# Microcontroller.net
KiCad netlist of a schematic drawn in Altium Designer
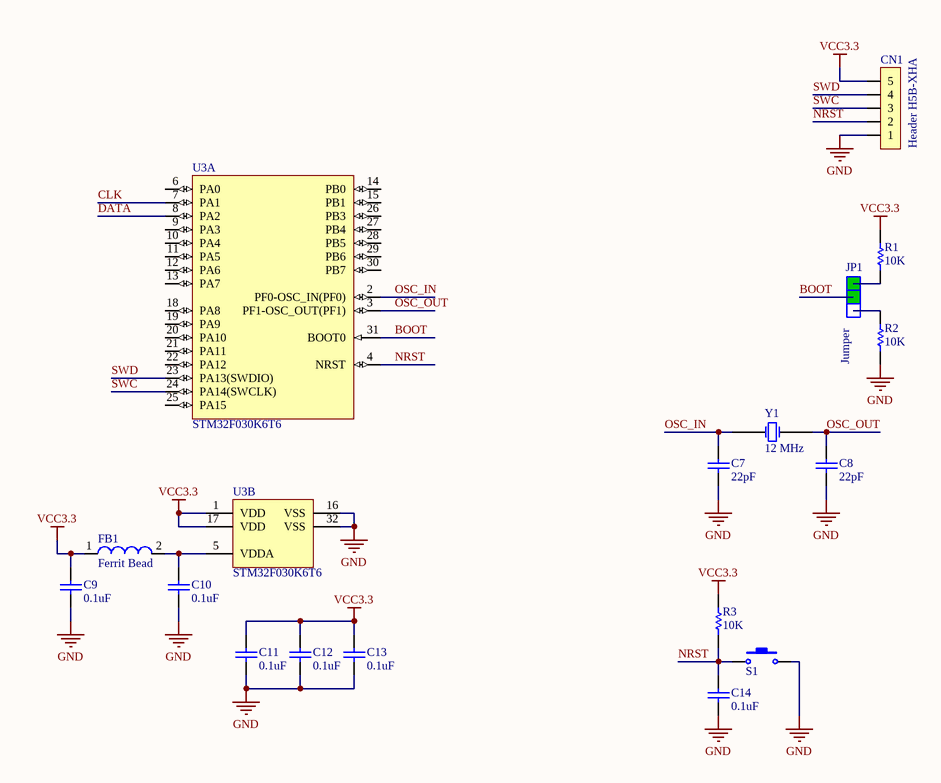
[diagram p0: Microcontroller.SchDoc]

(export (version "E")
  (design (tool "Eeschema 10.0.6"))
  (components
    (comp (ref "C7")
      (value "22pF")
      (footprint "CAPC4817X12N")
      (description "CAP 1206")
      (fields (field (name "DESIGNER") "Abbas Basereh"))
      (libsource (lib "2017AbbasBasereh9365731239 -ver1") (part "CAP SMD 1206"))
    )
    (comp (ref "C8")
      (value "22pF")
      (footprint "CAPC4817X12N")
      (description "CAP 1206")
      (fields (field (name "DESIGNER") "Abbas Basereh"))
      (libsource (lib "2017AbbasBasereh9365731239 -ver1") (part "CAP SMD 1206"))
    )
    (comp (ref "C9")
      (value "0.1uF")
      (footprint "CAPC4817X12N")
      (description "CAP 1206")
      (fields (field (name "DESIGNER") "Abbas Basereh"))
      (libsource (lib "2017AbbasBasereh9365731239 -ver1") (part "CAP SMD 1206"))
    )
    (comp (ref "C10")
      (value "0.1uF")
      (footprint "CAPC4817X12N")
      (description "CAP 1206")
      (fields (field (name "DESIGNER") "Abbas Basereh"))
      (libsource (lib "2017AbbasBasereh9365731239 -ver1") (part "CAP SMD 1206"))
    )
    (comp (ref "C11")
      (value "0.1uF")
      (footprint "CAPC4817X12N")
      (description "CAP 1206")
      (fields (field (name "DESIGNER") "Abbas Basereh"))
      (libsource (lib "2017AbbasBasereh9365731239 -ver1") (part "CAP SMD 1206"))
    )
    (comp (ref "C12")
      (value "0.1uF")
      (footprint "CAPC4817X12N")
      (description "CAP 1206")
      (fields (field (name "DESIGNER") "Abbas Basereh"))
      (libsource (lib "2017AbbasBasereh9365731239 -ver1") (part "CAP SMD 1206"))
    )
    (comp (ref "C13")
      (value "0.1uF")
      (footprint "CAPC4817X12N")
      (description "CAP 1206")
      (fields (field (name "DESIGNER") "Abbas Basereh"))
      (libsource (lib "2017AbbasBasereh9365731239 -ver1") (part "CAP SMD 1206"))
    )
    (comp (ref "C14")
      (value "0.1uF")
      (footprint "CAPC4817X12N")
      (description "CAP 1206")
      (fields (field (name "DESIGNER") "Abbas Basereh"))
      (libsource (lib "2017AbbasBasereh9365731239 -ver1") (part "CAP SMD 1206"))
    )
    (comp (ref "CN1")
      (value "Header H5B-XHA")
      (footprint "Header H5B-XHA")
      (libsource (lib "ZetaBoard_Lib") (part "Header H5B-XHA"))
    )
    (comp (ref "FB1")
      (value "Ferrit Bead")
      (footprint "1206 Ferrit Bead")
      (libsource (lib "ZetaBoard_Lib") (part "Ferrit Bead"))
    )
    (comp (ref "JP1")
      (value "Jumper")
      (footprint "Jumper Selector SMD")
      (description "Jumper Selector")
      (libsource (lib "Altium") (part "Jumper Selector"))
    )
    (comp (ref "R1")
      (value "10K")
      (footprint "RESC4817X04N")
      (description "RES 1206")
      (fields (field (name "DESIGNER") "Abbas Basereh"))
      (libsource (lib "2017AbbasBasereh9365731239 -ver1") (part "RES 1206 0.25W"))
    )
    (comp (ref "R2")
      (value "10K")
      (footprint "RESC4817X04N")
      (description "RES 1206")
      (fields (field (name "DESIGNER") "Abbas Basereh"))
      (libsource (lib "2017AbbasBasereh9365731239 -ver1") (part "RES 1206 0.25W"))
    )
    (comp (ref "R3")
      (value "10K")
      (footprint "RESC4817X04N")
      (description "RES 1206")
      (fields (field (name "DESIGNER") "Abbas Basereh"))
      (libsource (lib "2017AbbasBasereh9365731239 -ver1") (part "RES 1206 0.25W"))
    )
    (comp (ref "S1")
      (value "Switch PB")
      (footprint "Switch - Push to On")
      (description "Push Button Switch")
      (libsource (lib "Altium") (part "Switch PB"))
    )
    (comp (ref "U3")
      (value "STM32F030K6T6")
      (footprint "STM-LQFP32_N")
      (libsource (lib "STMicroelectronics STM32 F0") (part "STM32F030K6T6"))
    )
    (comp (ref "Y1")
      (value "12 MHz")
      (footprint "Crystal SMD")
      (description "XTAL Crystal")
      (fields (field (name "DESIGNER") "ABBAS BASEREH"))
      (libsource (lib "2017AbbasBasereh9365731239 -ver1") (part "XTAL_Crystal"))
    )
  )
  (nets
    (net (code "1") (name "/BOOT") (class "Default")
      (node (ref "JP1") (pin "2") (pinfunction "2_2") (pintype "passive"))
      (node (ref "U3") (pin "31") (pinfunction "BOOT0_31") (pintype "input"))
    )
    (net (code "2") (name "/CLK") (class "Default")
      (node (ref "U3") (pin "7") (pinfunction "PA1_7") (pintype "bidirectional"))
    )
    (net (code "3") (name "/DATA") (class "Default")
      (node (ref "U3") (pin "8") (pinfunction "PA2_8") (pintype "bidirectional"))
    )
    (net (code "4") (name "/NRST") (class "Default")
      (node (ref "C14") (pin "2") (pinfunction "2_2") (pintype "passive"))
      (node (ref "CN1") (pin "2") (pinfunction "2_2") (pintype "passive"))
      (node (ref "R3") (pin "1") (pinfunction "1_1") (pintype "passive"))
      (node (ref "S1") (pin "1") (pinfunction "1_1") (pintype "passive"))
      (node (ref "U3") (pin "4") (pinfunction "NRST_4") (pintype "bidirectional"))
    )
    (net (code "5") (name "/OSC_IN") (class "Default")
      (node (ref "C7") (pin "2") (pinfunction "2_2") (pintype "passive"))
      (node (ref "U3") (pin "2") (pinfunction "PF0-OSC_IN(PF0)_2") (pintype "bidirectional"))
      (node (ref "Y1") (pin "1") (pinfunction "OSC1_1") (pintype "passive"))
    )
    (net (code "6") (name "/OSC_OUT") (class "Default")
      (node (ref "C8") (pin "2") (pinfunction "2_2") (pintype "passive"))
      (node (ref "U3") (pin "3") (pinfunction "PF1-OSC_OUT(PF1)_3") (pintype "bidirectional"))
      (node (ref "Y1") (pin "2") (pinfunction "OSC2_2") (pintype "passive"))
    )
    (net (code "7") (name "/SWC") (class "Default")
      (node (ref "CN1") (pin "3") (pinfunction "3_3") (pintype "passive"))
      (node (ref "U3") (pin "24") (pinfunction "PA14(SWCLK)_24") (pintype "bidirectional"))
    )
    (net (code "8") (name "/SWD") (class "Default")
      (node (ref "CN1") (pin "4") (pinfunction "4_4") (pintype "passive"))
      (node (ref "U3") (pin "23") (pinfunction "PA13(SWDIO)_23") (pintype "bidirectional"))
    )
    (net (code "9") (name "GND") (class "Default")
      (node (ref "C10") (pin "1") (pinfunction "1_1") (pintype "passive"))
      (node (ref "C11") (pin "1") (pinfunction "1_1") (pintype "passive"))
      (node (ref "C12") (pin "1") (pinfunction "1_1") (pintype "passive"))
      (node (ref "C13") (pin "1") (pinfunction "1_1") (pintype "passive"))
      (node (ref "C14") (pin "1") (pinfunction "1_1") (pintype "passive"))
      (node (ref "C7") (pin "1") (pinfunction "1_1") (pintype "passive"))
      (node (ref "C8") (pin "1") (pinfunction "1_1") (pintype "passive"))
      (node (ref "C9") (pin "1") (pinfunction "1_1") (pintype "passive"))
      (node (ref "CN1") (pin "1") (pinfunction "1_1") (pintype "passive"))
      (node (ref "R2") (pin "1") (pinfunction "1_1") (pintype "passive"))
      (node (ref "S1") (pin "2") (pinfunction "2_2") (pintype "passive"))
      (node (ref "U3") (pin "16") (pinfunction "VSS_16") (pintype "power_in"))
      (node (ref "U3") (pin "32") (pinfunction "VSS_32") (pintype "power_in"))
    )
    (net (code "10") (name "Net-(JP1-Pad1)") (class "Default")
      (node (ref "JP1") (pin "1") (pinfunction "1_1") (pintype "passive"))
      (node (ref "R1") (pin "1") (pinfunction "1_1") (pintype "passive"))
    )
    (net (code "11") (name "Net-(JP1-Pad3)") (class "Default")
      (node (ref "JP1") (pin "3") (pinfunction "3_3") (pintype "passive"))
      (node (ref "R2") (pin "2") (pinfunction "2_2") (pintype "passive"))
    )
    (net (code "12") (name "Net-(U3B-VDDA)") (class "Default")
      (node (ref "C10") (pin "2") (pinfunction "2_2") (pintype "passive"))
      (node (ref "FB1") (pin "2") (pinfunction "2_2") (pintype "passive"))
      (node (ref "U3") (pin "5") (pinfunction "VDDA_5") (pintype "power_in"))
    )
    (net (code "13") (name "VCC3.3") (class "Default")
      (node (ref "C11") (pin "2") (pinfunction "2_2") (pintype "passive"))
      (node (ref "C12") (pin "2") (pinfunction "2_2") (pintype "passive"))
      (node (ref "C13") (pin "2") (pinfunction "2_2") (pintype "passive"))
      (node (ref "C9") (pin "2") (pinfunction "2_2") (pintype "passive"))
      (node (ref "CN1") (pin "5") (pinfunction "5_5") (pintype "passive"))
      (node (ref "FB1") (pin "1") (pinfunction "1_1") (pintype "passive"))
      (node (ref "R1") (pin "2") (pinfunction "2_2") (pintype "passive"))
      (node (ref "R3") (pin "2") (pinfunction "2_2") (pintype "passive"))
      (node (ref "U3") (pin "1") (pinfunction "VDD_1") (pintype "power_in"))
      (node (ref "U3") (pin "17") (pinfunction "VDD_17") (pintype "power_in"))
    )
    (net (code "14") (name "unconnected-(U3A-PA0-Pad6)") (class "Default")
      (node (ref "U3") (pin "6") (pinfunction "PA0_6") (pintype "bidirectional"))
    )
    (net (code "15") (name "unconnected-(U3A-PA3-Pad9)") (class "Default")
      (node (ref "U3") (pin "9") (pinfunction "PA3_9") (pintype "bidirectional"))
    )
    (net (code "16") (name "unconnected-(U3A-PA4-Pad10)") (class "Default")
      (node (ref "U3") (pin "10") (pinfunction "PA4_10") (pintype "bidirectional"))
    )
    (net (code "17") (name "unconnected-(U3A-PA5-Pad11)") (class "Default")
      (node (ref "U3") (pin "11") (pinfunction "PA5_11") (pintype "bidirectional"))
    )
    (net (code "18") (name "unconnected-(U3A-PA6-Pad12)") (class "Default")
      (node (ref "U3") (pin "12") (pinfunction "PA6_12") (pintype "bidirectional"))
    )
    (net (code "19") (name "unconnected-(U3A-PA7-Pad13)") (class "Default")
      (node (ref "U3") (pin "13") (pinfunction "PA7_13") (pintype "bidirectional"))
    )
    (net (code "20") (name "unconnected-(U3A-PA8-Pad18)") (class "Default")
      (node (ref "U3") (pin "18") (pinfunction "PA8_18") (pintype "bidirectional"))
    )
    (net (code "21") (name "unconnected-(U3A-PA9-Pad19)") (class "Default")
      (node (ref "U3") (pin "19") (pinfunction "PA9_19") (pintype "bidirectional"))
    )
    (net (code "22") (name "unconnected-(U3A-PA10-Pad20)") (class "Default")
      (node (ref "U3") (pin "20") (pinfunction "PA10_20") (pintype "bidirectional"))
    )
    (net (code "23") (name "unconnected-(U3A-PA11-Pad21)") (class "Default")
      (node (ref "U3") (pin "21") (pinfunction "PA11_21") (pintype "bidirectional"))
    )
    (net (code "24") (name "unconnected-(U3A-PA12-Pad22)") (class "Default")
      (node (ref "U3") (pin "22") (pinfunction "PA12_22") (pintype "bidirectional"))
    )
    (net (code "25") (name "unconnected-(U3A-PA15-Pad25)") (class "Default")
      (node (ref "U3") (pin "25") (pinfunction "PA15_25") (pintype "bidirectional"))
    )
    (net (code "26") (name "unconnected-(U3A-PB0-Pad14)") (class "Default")
      (node (ref "U3") (pin "14") (pinfunction "PB0_14") (pintype "bidirectional"))
    )
    (net (code "27") (name "unconnected-(U3A-PB1-Pad15)") (class "Default")
      (node (ref "U3") (pin "15") (pinfunction "PB1_15") (pintype "bidirectional"))
    )
    (net (code "28") (name "unconnected-(U3A-PB3-Pad26)") (class "Default")
      (node (ref "U3") (pin "26") (pinfunction "PB3_26") (pintype "bidirectional"))
    )
    (net (code "29") (name "unconnected-(U3A-PB4-Pad27)") (class "Default")
      (node (ref "U3") (pin "27") (pinfunction "PB4_27") (pintype "bidirectional"))
    )
    (net (code "30") (name "unconnected-(U3A-PB5-Pad28)") (class "Default")
      (node (ref "U3") (pin "28") (pinfunction "PB5_28") (pintype "bidirectional"))
    )
    (net (code "31") (name "unconnected-(U3A-PB6-Pad29)") (class "Default")
      (node (ref "U3") (pin "29") (pinfunction "PB6_29") (pintype "bidirectional"))
    )
    (net (code "32") (name "unconnected-(U3A-PB7-Pad30)") (class "Default")
      (node (ref "U3") (pin "30") (pinfunction "PB7_30") (pintype "bidirectional"))
    )
  )
)
